# nixie-board.net
KiCad netlist of a schematic drawn in EAGLE
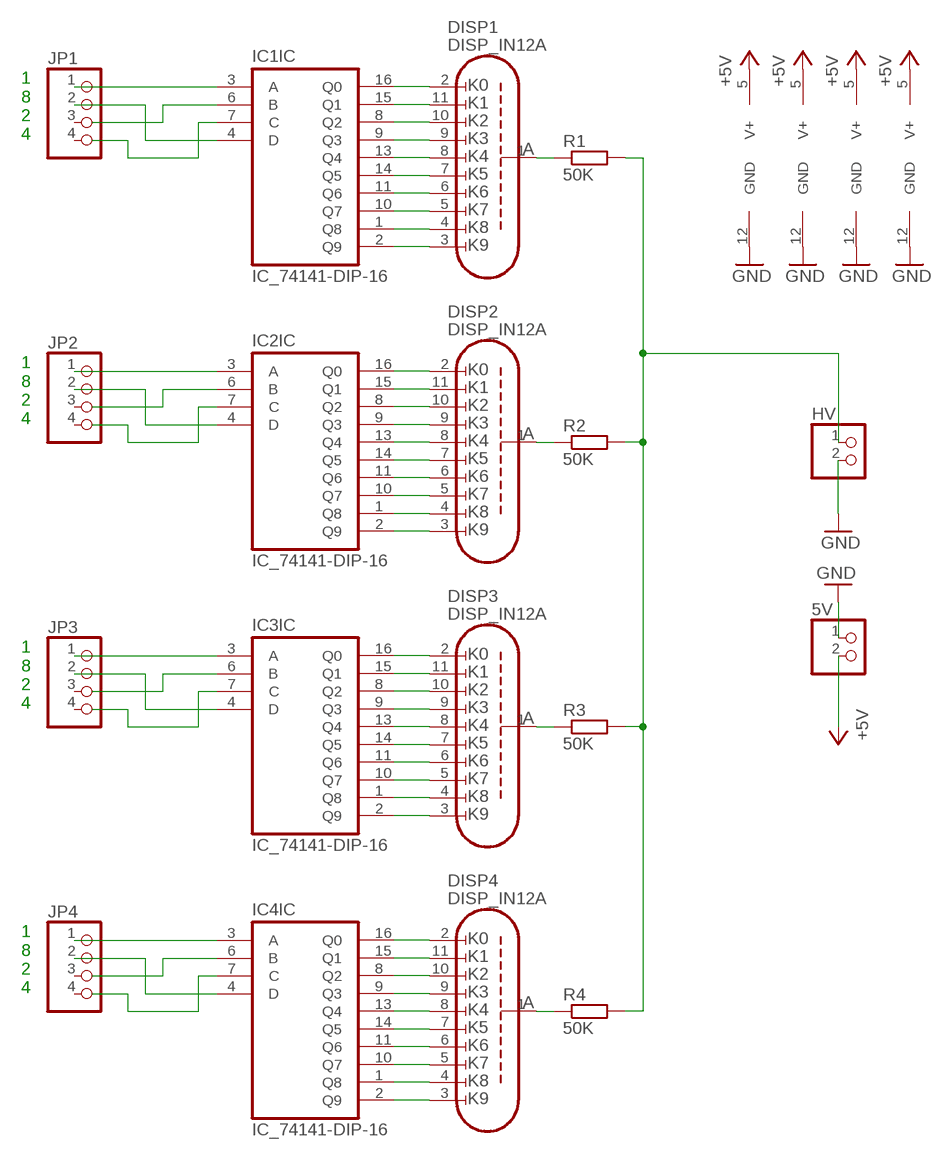
[diagram p0: schematic, sheet 1]

(export (version "E")
  (design (tool "Eeschema 10.0.6"))
  (components
    (comp (ref "5V")
      (value "PINHD-1X2")
      (footprint "eagle-import:1X02")
      (libsource (lib "eagle-import") (part "PINHD-1X2"))
    )
    (comp (ref "DISP1")
      (value "DISP_IN12A")
      (footprint "eagle-import:DISP_IN-12_SOCKET")
      (libsource (lib "eagle-import") (part "DISP_IN12A"))
    )
    (comp (ref "DISP2")
      (value "DISP_IN12A")
      (footprint "eagle-import:DISP_IN-12_SOCKET")
      (libsource (lib "eagle-import") (part "DISP_IN12A"))
    )
    (comp (ref "DISP3")
      (value "DISP_IN12A")
      (footprint "eagle-import:DISP_IN-12_SOCKET")
      (libsource (lib "eagle-import") (part "DISP_IN12A"))
    )
    (comp (ref "DISP4")
      (value "DISP_IN12A")
      (footprint "eagle-import:DISP_IN-12_SOCKET")
      (libsource (lib "eagle-import") (part "DISP_IN12A"))
    )
    (comp (ref "HV")
      (value "PINHD-1X2")
      (footprint "eagle-import:1X02")
      (libsource (lib "eagle-import") (part "PINHD-1X2"))
    )
    (comp (ref "IC1")
      (value "IC_74141-DIP-16")
      (footprint "eagle-import:DIL16")
      (libsource (lib "eagle-import") (part "IC_74141-DIP-16"))
    )
    (comp (ref "IC2")
      (value "IC_74141-DIP-16")
      (footprint "eagle-import:DIL16")
      (libsource (lib "eagle-import") (part "IC_74141-DIP-16"))
    )
    (comp (ref "IC3")
      (value "IC_74141-DIP-16")
      (footprint "eagle-import:DIL16")
      (libsource (lib "eagle-import") (part "IC_74141-DIP-16"))
    )
    (comp (ref "IC4")
      (value "IC_74141-DIP-16")
      (footprint "eagle-import:DIL16")
      (libsource (lib "eagle-import") (part "IC_74141-DIP-16"))
    )
    (comp (ref "IC5")
      (value "IC_74141-DIP-16")
      (footprint "eagle-import:DIL16")
      (libsource (lib "eagle-import") (part "IC_74141-DIP-16"))
    )
    (comp (ref "IC6")
      (value "IC_74141-DIP-16")
      (footprint "eagle-import:DIL16")
      (libsource (lib "eagle-import") (part "IC_74141-DIP-16"))
    )
    (comp (ref "IC7")
      (value "IC_74141-DIP-16")
      (footprint "eagle-import:DIL16")
      (libsource (lib "eagle-import") (part "IC_74141-DIP-16"))
    )
    (comp (ref "JP1")
      (value "PINHD-1X4")
      (footprint "eagle-import:1X04")
      (libsource (lib "eagle-import") (part "PINHD-1X4"))
    )
    (comp (ref "JP2")
      (value "PINHD-1X4")
      (footprint "eagle-import:1X04")
      (libsource (lib "eagle-import") (part "PINHD-1X4"))
    )
    (comp (ref "JP3")
      (value "PINHD-1X4")
      (footprint "eagle-import:1X04")
      (libsource (lib "eagle-import") (part "PINHD-1X4"))
    )
    (comp (ref "JP4")
      (value "PINHD-1X4")
      (footprint "eagle-import:1X04")
      (libsource (lib "eagle-import") (part "PINHD-1X4"))
    )
    (comp (ref "R1")
      (value "50K")
      (footprint "eagle-import:0207_12")
      (libsource (lib "eagle-import") (part "R-EU_0207/12"))
    )
    (comp (ref "R2")
      (value "50K")
      (footprint "eagle-import:0207_12")
      (libsource (lib "eagle-import") (part "R-EU_0207/12"))
    )
    (comp (ref "R3")
      (value "50K")
      (footprint "eagle-import:0207_12")
      (libsource (lib "eagle-import") (part "R-EU_0207/12"))
    )
    (comp (ref "R4")
      (value "50K")
      (footprint "eagle-import:0207_12")
      (libsource (lib "eagle-import") (part "R-EU_0207/12"))
    )
  )
  (nets
    (net (code "1") (name "+5V") (class "Default")
      (node (ref "5V") (pin "2") (pinfunction "2_2") (pintype "passive"))
      (node (ref "IC1") (pin "5") (pinfunction "V+_5") (pintype "power_in"))
      (node (ref "IC5") (pin "5") (pinfunction "V+_5") (pintype "power_in"))
      (node (ref "IC6") (pin "5") (pinfunction "V+_5") (pintype "power_in"))
      (node (ref "IC7") (pin "5") (pinfunction "V+_5") (pintype "power_in"))
    )
    (net (code "2") (name "GND") (class "Default")
      (node (ref "5V") (pin "1") (pinfunction "1_1") (pintype "passive"))
      (node (ref "HV") (pin "2") (pinfunction "2_2") (pintype "passive"))
      (node (ref "IC1") (pin "12") (pinfunction "GND_12") (pintype "power_in"))
      (node (ref "IC5") (pin "12") (pinfunction "GND_12") (pintype "power_in"))
      (node (ref "IC6") (pin "12") (pinfunction "GND_12") (pintype "power_in"))
      (node (ref "IC7") (pin "12") (pinfunction "GND_12") (pintype "power_in"))
    )
    (net (code "3") (name "Net-(DISP1-ANODE)") (class "Default")
      (node (ref "DISP1") (pin "1") (pinfunction "ANODE_1") (pintype "input"))
      (node (ref "R1") (pin "1") (pinfunction "1_1") (pintype "passive"))
    )
    (net (code "4") (name "Net-(DISP1-K0)") (class "Default")
      (node (ref "DISP1") (pin "2") (pinfunction "K0_2") (pintype "input"))
      (node (ref "IC1") (pin "16") (pinfunction "Q0_16") (pintype "output"))
    )
    (net (code "5") (name "Net-(DISP1-K1)") (class "Default")
      (node (ref "DISP1") (pin "11") (pinfunction "K1_11") (pintype "input"))
      (node (ref "IC1") (pin "15") (pinfunction "Q1_15") (pintype "output"))
    )
    (net (code "6") (name "Net-(DISP1-K2)") (class "Default")
      (node (ref "DISP1") (pin "10") (pinfunction "K2_10") (pintype "input"))
      (node (ref "IC1") (pin "8") (pinfunction "Q2_8") (pintype "output"))
    )
    (net (code "7") (name "Net-(DISP1-K3)") (class "Default")
      (node (ref "DISP1") (pin "9") (pinfunction "K3_9") (pintype "input"))
      (node (ref "IC1") (pin "9") (pinfunction "Q3_9") (pintype "output"))
    )
    (net (code "8") (name "Net-(DISP1-K4)") (class "Default")
      (node (ref "DISP1") (pin "8") (pinfunction "K4_8") (pintype "input"))
      (node (ref "IC1") (pin "13") (pinfunction "Q4_13") (pintype "output"))
    )
    (net (code "9") (name "Net-(DISP1-K5)") (class "Default")
      (node (ref "DISP1") (pin "7") (pinfunction "K5_7") (pintype "input"))
      (node (ref "IC1") (pin "14") (pinfunction "Q5_14") (pintype "output"))
    )
    (net (code "10") (name "Net-(DISP1-K6)") (class "Default")
      (node (ref "DISP1") (pin "6") (pinfunction "K6_6") (pintype "input"))
      (node (ref "IC1") (pin "11") (pinfunction "Q6_11") (pintype "output"))
    )
    (net (code "11") (name "Net-(DISP1-K7)") (class "Default")
      (node (ref "DISP1") (pin "5") (pinfunction "K7_5") (pintype "input"))
      (node (ref "IC1") (pin "10") (pinfunction "Q7_10") (pintype "output"))
    )
    (net (code "12") (name "Net-(DISP1-K8)") (class "Default")
      (node (ref "DISP1") (pin "4") (pinfunction "K8_4") (pintype "input"))
      (node (ref "IC1") (pin "1") (pinfunction "Q8_1") (pintype "output"))
    )
    (net (code "13") (name "Net-(DISP1-K9)") (class "Default")
      (node (ref "DISP1") (pin "3") (pinfunction "K9_3") (pintype "input"))
      (node (ref "IC1") (pin "2") (pinfunction "Q9_2") (pintype "output"))
    )
    (net (code "14") (name "Net-(DISP2-ANODE)") (class "Default")
      (node (ref "DISP2") (pin "1") (pinfunction "ANODE_1") (pintype "input"))
      (node (ref "R2") (pin "1") (pinfunction "1_1") (pintype "passive"))
    )
    (net (code "15") (name "Net-(DISP2-K0)") (class "Default")
      (node (ref "DISP2") (pin "2") (pinfunction "K0_2") (pintype "input"))
      (node (ref "IC2") (pin "16") (pinfunction "Q0_16") (pintype "output"))
    )
    (net (code "16") (name "Net-(DISP2-K1)") (class "Default")
      (node (ref "DISP2") (pin "11") (pinfunction "K1_11") (pintype "input"))
      (node (ref "IC2") (pin "15") (pinfunction "Q1_15") (pintype "output"))
    )
    (net (code "17") (name "Net-(DISP2-K2)") (class "Default")
      (node (ref "DISP2") (pin "10") (pinfunction "K2_10") (pintype "input"))
      (node (ref "IC2") (pin "8") (pinfunction "Q2_8") (pintype "output"))
    )
    (net (code "18") (name "Net-(DISP2-K3)") (class "Default")
      (node (ref "DISP2") (pin "9") (pinfunction "K3_9") (pintype "input"))
      (node (ref "IC2") (pin "9") (pinfunction "Q3_9") (pintype "output"))
    )
    (net (code "19") (name "Net-(DISP2-K4)") (class "Default")
      (node (ref "DISP2") (pin "8") (pinfunction "K4_8") (pintype "input"))
      (node (ref "IC2") (pin "13") (pinfunction "Q4_13") (pintype "output"))
    )
    (net (code "20") (name "Net-(DISP2-K5)") (class "Default")
      (node (ref "DISP2") (pin "7") (pinfunction "K5_7") (pintype "input"))
      (node (ref "IC2") (pin "14") (pinfunction "Q5_14") (pintype "output"))
    )
    (net (code "21") (name "Net-(DISP2-K6)") (class "Default")
      (node (ref "DISP2") (pin "6") (pinfunction "K6_6") (pintype "input"))
      (node (ref "IC2") (pin "11") (pinfunction "Q6_11") (pintype "output"))
    )
    (net (code "22") (name "Net-(DISP2-K7)") (class "Default")
      (node (ref "DISP2") (pin "5") (pinfunction "K7_5") (pintype "input"))
      (node (ref "IC2") (pin "10") (pinfunction "Q7_10") (pintype "output"))
    )
    (net (code "23") (name "Net-(DISP2-K8)") (class "Default")
      (node (ref "DISP2") (pin "4") (pinfunction "K8_4") (pintype "input"))
      (node (ref "IC2") (pin "1") (pinfunction "Q8_1") (pintype "output"))
    )
    (net (code "24") (name "Net-(DISP2-K9)") (class "Default")
      (node (ref "DISP2") (pin "3") (pinfunction "K9_3") (pintype "input"))
      (node (ref "IC2") (pin "2") (pinfunction "Q9_2") (pintype "output"))
    )
    (net (code "25") (name "Net-(DISP3-ANODE)") (class "Default")
      (node (ref "DISP3") (pin "1") (pinfunction "ANODE_1") (pintype "input"))
      (node (ref "R3") (pin "1") (pinfunction "1_1") (pintype "passive"))
    )
    (net (code "26") (name "Net-(DISP3-K0)") (class "Default")
      (node (ref "DISP3") (pin "2") (pinfunction "K0_2") (pintype "input"))
      (node (ref "IC3") (pin "16") (pinfunction "Q0_16") (pintype "output"))
    )
    (net (code "27") (name "Net-(DISP3-K1)") (class "Default")
      (node (ref "DISP3") (pin "11") (pinfunction "K1_11") (pintype "input"))
      (node (ref "IC3") (pin "15") (pinfunction "Q1_15") (pintype "output"))
    )
    (net (code "28") (name "Net-(DISP3-K2)") (class "Default")
      (node (ref "DISP3") (pin "10") (pinfunction "K2_10") (pintype "input"))
      (node (ref "IC3") (pin "8") (pinfunction "Q2_8") (pintype "output"))
    )
    (net (code "29") (name "Net-(DISP3-K3)") (class "Default")
      (node (ref "DISP3") (pin "9") (pinfunction "K3_9") (pintype "input"))
      (node (ref "IC3") (pin "9") (pinfunction "Q3_9") (pintype "output"))
    )
    (net (code "30") (name "Net-(DISP3-K4)") (class "Default")
      (node (ref "DISP3") (pin "8") (pinfunction "K4_8") (pintype "input"))
      (node (ref "IC3") (pin "13") (pinfunction "Q4_13") (pintype "output"))
    )
    (net (code "31") (name "Net-(DISP3-K5)") (class "Default")
      (node (ref "DISP3") (pin "7") (pinfunction "K5_7") (pintype "input"))
      (node (ref "IC3") (pin "14") (pinfunction "Q5_14") (pintype "output"))
    )
    (net (code "32") (name "Net-(DISP3-K6)") (class "Default")
      (node (ref "DISP3") (pin "6") (pinfunction "K6_6") (pintype "input"))
      (node (ref "IC3") (pin "11") (pinfunction "Q6_11") (pintype "output"))
    )
    (net (code "33") (name "Net-(DISP3-K7)") (class "Default")
      (node (ref "DISP3") (pin "5") (pinfunction "K7_5") (pintype "input"))
      (node (ref "IC3") (pin "10") (pinfunction "Q7_10") (pintype "output"))
    )
    (net (code "34") (name "Net-(DISP3-K8)") (class "Default")
      (node (ref "DISP3") (pin "4") (pinfunction "K8_4") (pintype "input"))
      (node (ref "IC3") (pin "1") (pinfunction "Q8_1") (pintype "output"))
    )
    (net (code "35") (name "Net-(DISP3-K9)") (class "Default")
      (node (ref "DISP3") (pin "3") (pinfunction "K9_3") (pintype "input"))
      (node (ref "IC3") (pin "2") (pinfunction "Q9_2") (pintype "output"))
    )
    (net (code "36") (name "Net-(DISP4-ANODE)") (class "Default")
      (node (ref "DISP4") (pin "1") (pinfunction "ANODE_1") (pintype "input"))
      (node (ref "R4") (pin "1") (pinfunction "1_1") (pintype "passive"))
    )
    (net (code "37") (name "Net-(DISP4-K0)") (class "Default")
      (node (ref "DISP4") (pin "2") (pinfunction "K0_2") (pintype "input"))
      (node (ref "IC4") (pin "16") (pinfunction "Q0_16") (pintype "output"))
    )
    (net (code "38") (name "Net-(DISP4-K1)") (class "Default")
      (node (ref "DISP4") (pin "11") (pinfunction "K1_11") (pintype "input"))
      (node (ref "IC4") (pin "15") (pinfunction "Q1_15") (pintype "output"))
    )
    (net (code "39") (name "Net-(DISP4-K2)") (class "Default")
      (node (ref "DISP4") (pin "10") (pinfunction "K2_10") (pintype "input"))
      (node (ref "IC4") (pin "8") (pinfunction "Q2_8") (pintype "output"))
    )
    (net (code "40") (name "Net-(DISP4-K3)") (class "Default")
      (node (ref "DISP4") (pin "9") (pinfunction "K3_9") (pintype "input"))
      (node (ref "IC4") (pin "9") (pinfunction "Q3_9") (pintype "output"))
    )
    (net (code "41") (name "Net-(DISP4-K4)") (class "Default")
      (node (ref "DISP4") (pin "8") (pinfunction "K4_8") (pintype "input"))
      (node (ref "IC4") (pin "13") (pinfunction "Q4_13") (pintype "output"))
    )
    (net (code "42") (name "Net-(DISP4-K5)") (class "Default")
      (node (ref "DISP4") (pin "7") (pinfunction "K5_7") (pintype "input"))
      (node (ref "IC4") (pin "14") (pinfunction "Q5_14") (pintype "output"))
    )
    (net (code "43") (name "Net-(DISP4-K6)") (class "Default")
      (node (ref "DISP4") (pin "6") (pinfunction "K6_6") (pintype "input"))
      (node (ref "IC4") (pin "11") (pinfunction "Q6_11") (pintype "output"))
    )
    (net (code "44") (name "Net-(DISP4-K7)") (class "Default")
      (node (ref "DISP4") (pin "5") (pinfunction "K7_5") (pintype "input"))
      (node (ref "IC4") (pin "10") (pinfunction "Q7_10") (pintype "output"))
    )
    (net (code "45") (name "Net-(DISP4-K8)") (class "Default")
      (node (ref "DISP4") (pin "4") (pinfunction "K8_4") (pintype "input"))
      (node (ref "IC4") (pin "1") (pinfunction "Q8_1") (pintype "output"))
    )
    (net (code "46") (name "Net-(DISP4-K9)") (class "Default")
      (node (ref "DISP4") (pin "3") (pinfunction "K9_3") (pintype "input"))
      (node (ref "IC4") (pin "2") (pinfunction "Q9_2") (pintype "output"))
    )
    (net (code "47") (name "Net-(HV-Pad1)") (class "Default")
      (node (ref "HV") (pin "1") (pinfunction "1_1") (pintype "passive"))
      (node (ref "R1") (pin "2") (pinfunction "2_2") (pintype "passive"))
      (node (ref "R2") (pin "2") (pinfunction "2_2") (pintype "passive"))
      (node (ref "R3") (pin "2") (pinfunction "2_2") (pintype "passive"))
      (node (ref "R4") (pin "2") (pinfunction "2_2") (pintype "passive"))
    )
    (net (code "48") (name "Net-(IC1A-A)") (class "Default")
      (node (ref "IC1") (pin "3") (pinfunction "A_3") (pintype "input"))
      (node (ref "JP1") (pin "1") (pinfunction "1_1") (pintype "passive"))
    )
    (net (code "49") (name "Net-(IC1A-D)") (class "Default")
      (node (ref "IC1") (pin "4") (pinfunction "D_4") (pintype "input"))
      (node (ref "JP1") (pin "2") (pinfunction "2_2") (pintype "passive"))
    )
    (net (code "50") (name "Net-(IC2A-A)") (class "Default")
      (node (ref "IC2") (pin "3") (pinfunction "A_3") (pintype "input"))
      (node (ref "JP2") (pin "1") (pinfunction "1_1") (pintype "passive"))
    )
    (net (code "51") (name "Net-(IC2A-D)") (class "Default")
      (node (ref "IC2") (pin "4") (pinfunction "D_4") (pintype "input"))
      (node (ref "JP2") (pin "2") (pinfunction "2_2") (pintype "passive"))
    )
    (net (code "52") (name "Net-(IC3A-A)") (class "Default")
      (node (ref "IC3") (pin "3") (pinfunction "A_3") (pintype "input"))
      (node (ref "JP3") (pin "1") (pinfunction "1_1") (pintype "passive"))
    )
    (net (code "53") (name "Net-(IC3A-D)") (class "Default")
      (node (ref "IC3") (pin "4") (pinfunction "D_4") (pintype "input"))
      (node (ref "JP3") (pin "2") (pinfunction "2_2") (pintype "passive"))
    )
    (net (code "54") (name "Net-(IC4A-A)") (class "Default")
      (node (ref "IC4") (pin "3") (pinfunction "A_3") (pintype "input"))
      (node (ref "JP4") (pin "1") (pinfunction "1_1") (pintype "passive"))
    )
    (net (code "55") (name "Net-(IC4A-D)") (class "Default")
      (node (ref "IC4") (pin "4") (pinfunction "D_4") (pintype "input"))
      (node (ref "JP4") (pin "2") (pinfunction "2_2") (pintype "passive"))
    )
    (net (code "56") (name "unconnected-(IC1A-B-Pad6)") (class "Default")
      (node (ref "IC1") (pin "6") (pinfunction "B_6") (pintype "input"))
    )
    (net (code "57") (name "unconnected-(IC1A-C-Pad7)") (class "Default")
      (node (ref "IC1") (pin "7") (pinfunction "C_7") (pintype "input"))
    )
    (net (code "58") (name "unconnected-(IC2A-B-Pad6)") (class "Default")
      (node (ref "IC2") (pin "6") (pinfunction "B_6") (pintype "input"))
    )
    (net (code "59") (name "unconnected-(IC2A-C-Pad7)") (class "Default")
      (node (ref "IC2") (pin "7") (pinfunction "C_7") (pintype "input"))
    )
    (net (code "60") (name "unconnected-(IC3A-B-Pad6)") (class "Default")
      (node (ref "IC3") (pin "6") (pinfunction "B_6") (pintype "input"))
    )
    (net (code "61") (name "unconnected-(IC3A-C-Pad7)") (class "Default")
      (node (ref "IC3") (pin "7") (pinfunction "C_7") (pintype "input"))
    )
    (net (code "62") (name "unconnected-(IC4A-B-Pad6)") (class "Default")
      (node (ref "IC4") (pin "6") (pinfunction "B_6") (pintype "input"))
    )
    (net (code "63") (name "unconnected-(IC4A-C-Pad7)") (class "Default")
      (node (ref "IC4") (pin "7") (pinfunction "C_7") (pintype "input"))
    )
    (net (code "64") (name "unconnected-(JP1-Pad3)") (class "Default")
      (node (ref "JP1") (pin "3") (pinfunction "3_3") (pintype "passive"))
    )
    (net (code "65") (name "unconnected-(JP1-Pad4)") (class "Default")
      (node (ref "JP1") (pin "4") (pinfunction "4_4") (pintype "passive"))
    )
    (net (code "66") (name "unconnected-(JP2-Pad3)") (class "Default")
      (node (ref "JP2") (pin "3") (pinfunction "3_3") (pintype "passive"))
    )
    (net (code "67") (name "unconnected-(JP2-Pad4)") (class "Default")
      (node (ref "JP2") (pin "4") (pinfunction "4_4") (pintype "passive"))
    )
    (net (code "68") (name "unconnected-(JP3-Pad3)") (class "Default")
      (node (ref "JP3") (pin "3") (pinfunction "3_3") (pintype "passive"))
    )
    (net (code "69") (name "unconnected-(JP3-Pad4)") (class "Default")
      (node (ref "JP3") (pin "4") (pinfunction "4_4") (pintype "passive"))
    )
    (net (code "70") (name "unconnected-(JP4-Pad3)") (class "Default")
      (node (ref "JP4") (pin "3") (pinfunction "3_3") (pintype "passive"))
    )
    (net (code "71") (name "unconnected-(JP4-Pad4)") (class "Default")
      (node (ref "JP4") (pin "4") (pinfunction "4_4") (pintype "passive"))
    )
  )
)
